# Microcontroller_Schematic.net
KiCad netlist of a schematic drawn in Altium Designer
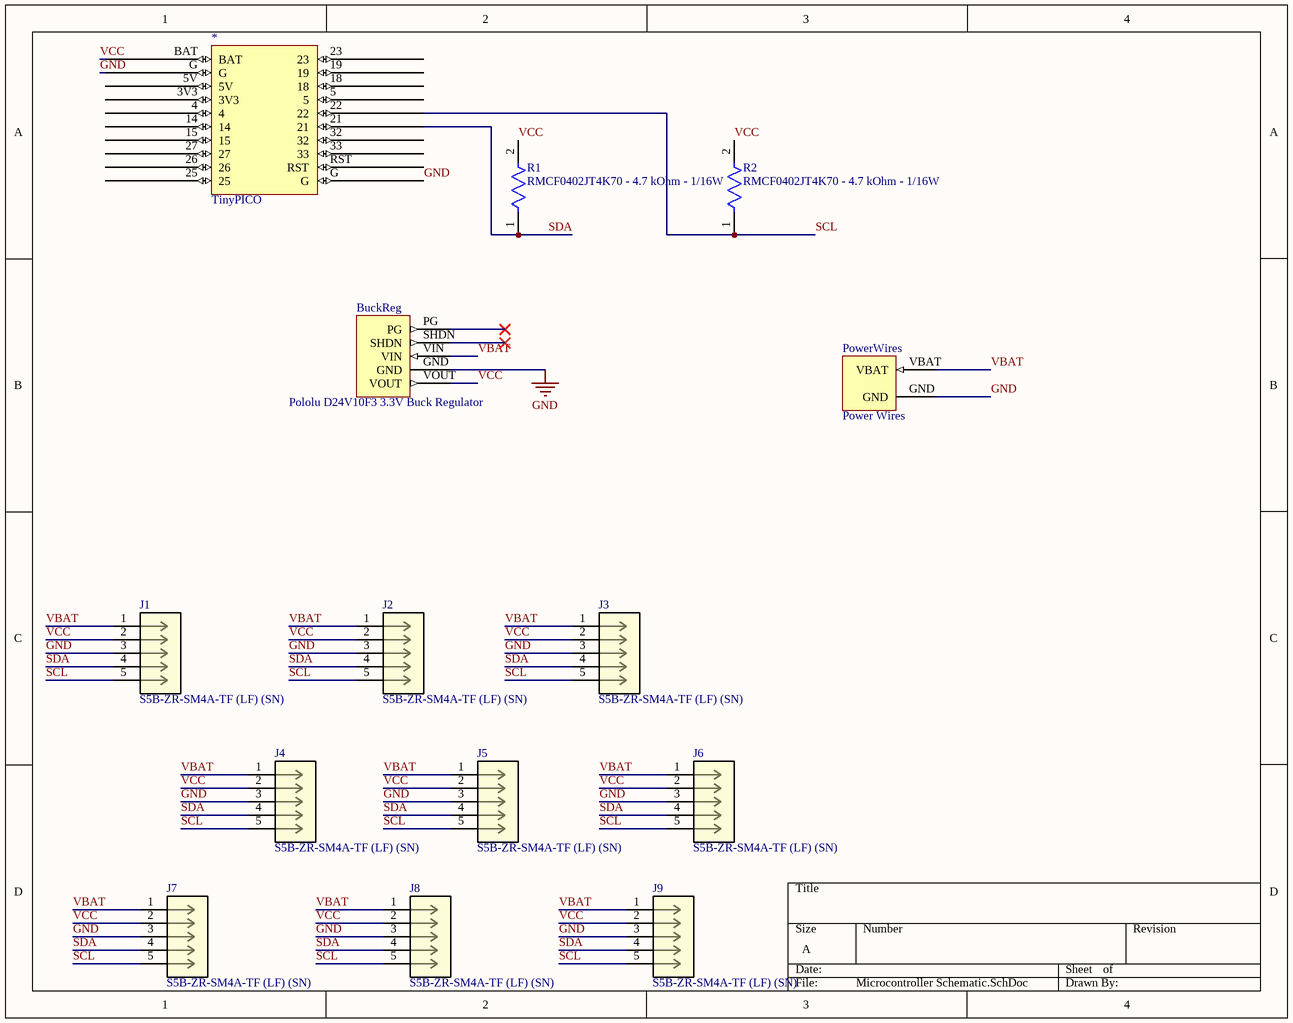
[diagram p0: Microcontroller Schematic.SchDoc]

(export (version "E")
  (design (tool "Eeschema 10.0.6"))
  (components
    (comp (ref "*")
      (value "TinyPICO")
      (footprint "TinyPICO Board")
      (libsource (lib "TinyPICO") (part "TinyPICO"))
    )
    (comp (ref "BuckReg")
      (value "Pololu D24V10F3 3.3V Buck Regulator")
      (footprint "PCBComponent_1")
      (libsource (lib "Pololu Step Down Voltage Regulator") (part "Component_1"))
    )
    (comp (ref "J1")
      (value "S5B-ZR-SM4A-TF (LF) (SN)")
      (footprint "CONN_S5B-ZR-SM4A-TF_JST")
      (description "No Description Available")
      (fields (field (name "COPYRIGHT") "Copyright (C) 2021 Ultra Librarian. All rights reserved."))
      (libsource (lib "S5B-ZR-SM4A-TF_LF__SN_") (part "S5B-ZR-SM4A-TF (LF) (SN)"))
    )
    (comp (ref "J2")
      (value "S5B-ZR-SM4A-TF (LF) (SN)")
      (footprint "CONN_S5B-ZR-SM4A-TF_JST")
      (description "No Description Available")
      (fields (field (name "COPYRIGHT") "Copyright (C) 2021 Ultra Librarian. All rights reserved."))
      (libsource (lib "S5B-ZR-SM4A-TF_LF__SN_") (part "S5B-ZR-SM4A-TF (LF) (SN)"))
    )
    (comp (ref "J3")
      (value "S5B-ZR-SM4A-TF (LF) (SN)")
      (footprint "CONN_S5B-ZR-SM4A-TF_JST")
      (description "No Description Available")
      (fields (field (name "COPYRIGHT") "Copyright (C) 2021 Ultra Librarian. All rights reserved."))
      (libsource (lib "S5B-ZR-SM4A-TF_LF__SN_") (part "S5B-ZR-SM4A-TF (LF) (SN)"))
    )
    (comp (ref "J4")
      (value "S5B-ZR-SM4A-TF (LF) (SN)")
      (footprint "CONN_S5B-ZR-SM4A-TF_JST")
      (description "No Description Available")
      (fields (field (name "COPYRIGHT") "Copyright (C) 2021 Ultra Librarian. All rights reserved."))
      (libsource (lib "S5B-ZR-SM4A-TF_LF__SN_") (part "S5B-ZR-SM4A-TF (LF) (SN)"))
    )
    (comp (ref "J5")
      (value "S5B-ZR-SM4A-TF (LF) (SN)")
      (footprint "CONN_S5B-ZR-SM4A-TF_JST")
      (description "No Description Available")
      (fields (field (name "COPYRIGHT") "Copyright (C) 2021 Ultra Librarian. All rights reserved."))
      (libsource (lib "S5B-ZR-SM4A-TF_LF__SN_") (part "S5B-ZR-SM4A-TF (LF) (SN)"))
    )
    (comp (ref "J6")
      (value "S5B-ZR-SM4A-TF (LF) (SN)")
      (footprint "CONN_S5B-ZR-SM4A-TF_JST")
      (description "No Description Available")
      (fields (field (name "COPYRIGHT") "Copyright (C) 2021 Ultra Librarian. All rights reserved."))
      (libsource (lib "S5B-ZR-SM4A-TF_LF__SN_") (part "S5B-ZR-SM4A-TF (LF) (SN)"))
    )
    (comp (ref "J7")
      (value "S5B-ZR-SM4A-TF (LF) (SN)")
      (footprint "CONN_S5B-ZR-SM4A-TF_JST")
      (description "No Description Available")
      (fields (field (name "COPYRIGHT") "Copyright (C) 2021 Ultra Librarian. All rights reserved."))
      (libsource (lib "S5B-ZR-SM4A-TF_LF__SN_") (part "S5B-ZR-SM4A-TF (LF) (SN)"))
    )
    (comp (ref "J8")
      (value "S5B-ZR-SM4A-TF (LF) (SN)")
      (footprint "CONN_S5B-ZR-SM4A-TF_JST")
      (description "No Description Available")
      (fields (field (name "COPYRIGHT") "Copyright (C) 2021 Ultra Librarian. All rights reserved."))
      (libsource (lib "S5B-ZR-SM4A-TF_LF__SN_") (part "S5B-ZR-SM4A-TF (LF) (SN)"))
    )
    (comp (ref "J9")
      (value "S5B-ZR-SM4A-TF (LF) (SN)")
      (footprint "CONN_S5B-ZR-SM4A-TF_JST")
      (description "No Description Available")
      (fields (field (name "COPYRIGHT") "Copyright (C) 2021 Ultra Librarian. All rights reserved."))
      (libsource (lib "S5B-ZR-SM4A-TF_LF__SN_") (part "S5B-ZR-SM4A-TF (LF) (SN)"))
    )
    (comp (ref "PowerWires")
      (value "Power Wires")
      (footprint "Power Wires")
      (libsource (lib "Power Wires") (part "Component_1"))
    )
    (comp (ref "R1")
      (value "RMCF0402JT4K70 - 4.7 kOhm - 1/16W")
      (footprint "FP-RMCF0402-MFG")
      (description "4.7kΩ ±5% 0.063W 0402 Thick Film Chip Resistor AEC-Q200 compliant")
      (fields (field (name "TOLERANCE") "5%"))
      (libsource (lib "Altium Content Vault") (part "1029c3af85768c4190bb7ad29bc67b5"))
    )
    (comp (ref "R2")
      (value "RMCF0402JT4K70 - 4.7 kOhm - 1/16W")
      (footprint "FP-RMCF0402-MFG")
      (description "4.7kΩ ±5% 0.063W 0402 Thick Film Chip Resistor AEC-Q200 compliant")
      (fields (field (name "TOLERANCE") "5%"))
      (libsource (lib "Altium Content Vault") (part "1029c3af85768c4190bb7ad29bc67b5"))
    )
  )
  (nets
    (net (code "1") (name "/SCL") (class "Default")
      (node (ref "*") (pin "22") (pinfunction "22_22") (pintype "bidirectional"))
      (node (ref "J1") (pin "5") (pinfunction "5_5") (pintype "passive"))
      (node (ref "J2") (pin "5") (pinfunction "5_5") (pintype "passive"))
      (node (ref "J3") (pin "5") (pinfunction "5_5") (pintype "passive"))
      (node (ref "J4") (pin "5") (pinfunction "5_5") (pintype "passive"))
      (node (ref "J5") (pin "5") (pinfunction "5_5") (pintype "passive"))
      (node (ref "J6") (pin "5") (pinfunction "5_5") (pintype "passive"))
      (node (ref "J7") (pin "5") (pinfunction "5_5") (pintype "passive"))
      (node (ref "J8") (pin "5") (pinfunction "5_5") (pintype "passive"))
      (node (ref "J9") (pin "5") (pinfunction "5_5") (pintype "passive"))
      (node (ref "R2") (pin "1") (pinfunction "1_1") (pintype "passive"))
    )
    (net (code "2") (name "/SDA") (class "Default")
      (node (ref "*") (pin "21") (pinfunction "21_21") (pintype "bidirectional"))
      (node (ref "J1") (pin "4") (pinfunction "4_4") (pintype "passive"))
      (node (ref "J2") (pin "4") (pinfunction "4_4") (pintype "passive"))
      (node (ref "J3") (pin "4") (pinfunction "4_4") (pintype "passive"))
      (node (ref "J4") (pin "4") (pinfunction "4_4") (pintype "passive"))
      (node (ref "J5") (pin "4") (pinfunction "4_4") (pintype "passive"))
      (node (ref "J6") (pin "4") (pinfunction "4_4") (pintype "passive"))
      (node (ref "J7") (pin "4") (pinfunction "4_4") (pintype "passive"))
      (node (ref "J8") (pin "4") (pinfunction "4_4") (pintype "passive"))
      (node (ref "J9") (pin "4") (pinfunction "4_4") (pintype "passive"))
      (node (ref "R1") (pin "1") (pinfunction "1_1") (pintype "passive"))
    )
    (net (code "3") (name "/VBAT") (class "Default")
      (node (ref "BuckReg") (pin "VIN") (pinfunction "VIN_VIN") (pintype "input"))
      (node (ref "J1") (pin "1") (pinfunction "1_1") (pintype "passive"))
      (node (ref "J2") (pin "1") (pinfunction "1_1") (pintype "passive"))
      (node (ref "J3") (pin "1") (pinfunction "1_1") (pintype "passive"))
      (node (ref "J4") (pin "1") (pinfunction "1_1") (pintype "passive"))
      (node (ref "J5") (pin "1") (pinfunction "1_1") (pintype "passive"))
      (node (ref "J6") (pin "1") (pinfunction "1_1") (pintype "passive"))
      (node (ref "J7") (pin "1") (pinfunction "1_1") (pintype "passive"))
      (node (ref "J8") (pin "1") (pinfunction "1_1") (pintype "passive"))
      (node (ref "J9") (pin "1") (pinfunction "1_1") (pintype "passive"))
      (node (ref "PowerWires") (pin "VBAT") (pinfunction "VBAT_VBAT") (pintype "input"))
    )
    (net (code "4") (name "/VCC") (class "Default")
      (node (ref "*") (pin "BAT") (pinfunction "BAT_BAT") (pintype "bidirectional"))
      (node (ref "BuckReg") (pin "VOUT") (pinfunction "VOUT_VOUT") (pintype "output"))
      (node (ref "J1") (pin "2") (pinfunction "2_2") (pintype "passive"))
      (node (ref "J2") (pin "2") (pinfunction "2_2") (pintype "passive"))
      (node (ref "J3") (pin "2") (pinfunction "2_2") (pintype "passive"))
      (node (ref "J4") (pin "2") (pinfunction "2_2") (pintype "passive"))
      (node (ref "J5") (pin "2") (pinfunction "2_2") (pintype "passive"))
      (node (ref "J6") (pin "2") (pinfunction "2_2") (pintype "passive"))
      (node (ref "J7") (pin "2") (pinfunction "2_2") (pintype "passive"))
      (node (ref "J8") (pin "2") (pinfunction "2_2") (pintype "passive"))
      (node (ref "J9") (pin "2") (pinfunction "2_2") (pintype "passive"))
      (node (ref "R1") (pin "2") (pinfunction "2_2") (pintype "passive"))
      (node (ref "R2") (pin "2") (pinfunction "2_2") (pintype "passive"))
    )
    (net (code "5") (name "GND") (class "Default")
      (node (ref "*") (pin "G") (pinfunction "G_G") (pintype "bidirectional"))
      (node (ref "BuckReg") (pin "GND") (pinfunction "GND_GND") (pintype "passive"))
      (node (ref "J1") (pin "3") (pinfunction "3_3") (pintype "passive"))
      (node (ref "J2") (pin "3") (pinfunction "3_3") (pintype "passive"))
      (node (ref "J3") (pin "3") (pinfunction "3_3") (pintype "passive"))
      (node (ref "J4") (pin "3") (pinfunction "3_3") (pintype "passive"))
      (node (ref "J5") (pin "3") (pinfunction "3_3") (pintype "passive"))
      (node (ref "J6") (pin "3") (pinfunction "3_3") (pintype "passive"))
      (node (ref "J7") (pin "3") (pinfunction "3_3") (pintype "passive"))
      (node (ref "J8") (pin "3") (pinfunction "3_3") (pintype "passive"))
      (node (ref "J9") (pin "3") (pinfunction "3_3") (pintype "passive"))
      (node (ref "PowerWires") (pin "GND") (pinfunction "GND_GND") (pintype "passive"))
    )
    (net (code "6") (name "unconnected-(*-Pad3V3)") (class "Default")
      (node (ref "*") (pin "3V3") (pinfunction "3V3_3V3") (pintype "bidirectional"))
    )
    (net (code "7") (name "unconnected-(*-Pad4)") (class "Default")
      (node (ref "*") (pin "4") (pinfunction "4_4") (pintype "bidirectional"))
    )
    (net (code "8") (name "unconnected-(*-Pad5)") (class "Default")
      (node (ref "*") (pin "5") (pinfunction "5_5") (pintype "bidirectional"))
    )
    (net (code "9") (name "unconnected-(*-Pad5V)") (class "Default")
      (node (ref "*") (pin "5V") (pinfunction "5V_5V") (pintype "bidirectional"))
    )
    (net (code "10") (name "unconnected-(*-Pad14)") (class "Default")
      (node (ref "*") (pin "14") (pinfunction "14_14") (pintype "bidirectional"))
    )
    (net (code "11") (name "unconnected-(*-Pad15)") (class "Default")
      (node (ref "*") (pin "15") (pinfunction "15_15") (pintype "bidirectional"))
    )
    (net (code "12") (name "unconnected-(*-Pad18)") (class "Default")
      (node (ref "*") (pin "18") (pinfunction "18_18") (pintype "bidirectional"))
    )
    (net (code "13") (name "unconnected-(*-Pad19)") (class "Default")
      (node (ref "*") (pin "19") (pinfunction "19_19") (pintype "bidirectional"))
    )
    (net (code "14") (name "unconnected-(*-Pad23)") (class "Default")
      (node (ref "*") (pin "23") (pinfunction "23_23") (pintype "bidirectional"))
    )
    (net (code "15") (name "unconnected-(*-Pad25)") (class "Default")
      (node (ref "*") (pin "25") (pinfunction "25_25") (pintype "bidirectional"))
    )
    (net (code "16") (name "unconnected-(*-Pad26)") (class "Default")
      (node (ref "*") (pin "26") (pinfunction "26_26") (pintype "bidirectional"))
    )
    (net (code "17") (name "unconnected-(*-Pad27)") (class "Default")
      (node (ref "*") (pin "27") (pinfunction "27_27") (pintype "bidirectional"))
    )
    (net (code "18") (name "unconnected-(*-Pad32)") (class "Default")
      (node (ref "*") (pin "32") (pinfunction "32_32") (pintype "bidirectional"))
    )
    (net (code "19") (name "unconnected-(*-Pad33)") (class "Default")
      (node (ref "*") (pin "33") (pinfunction "33_33") (pintype "bidirectional"))
    )
    (net (code "20") (name "unconnected-(*-PadRST)") (class "Default")
      (node (ref "*") (pin "RST") (pinfunction "RST_RST") (pintype "bidirectional"))
    )
    (net (code "21") (name "unconnected-(BuckReg-PadPG)") (class "Default")
      (node (ref "BuckReg") (pin "PG") (pinfunction "PG_PG") (pintype "output+no_connect"))
    )
    (net (code "22") (name "unconnected-(BuckReg-PadSHDN)") (class "Default")
      (node (ref "BuckReg") (pin "SHDN") (pinfunction "SHDN_SHDN") (pintype "output+no_connect"))
    )
  )
)
